# u16c_ubus_rev_b.net
KiCad netlist of a schematic drawn in EAGLE
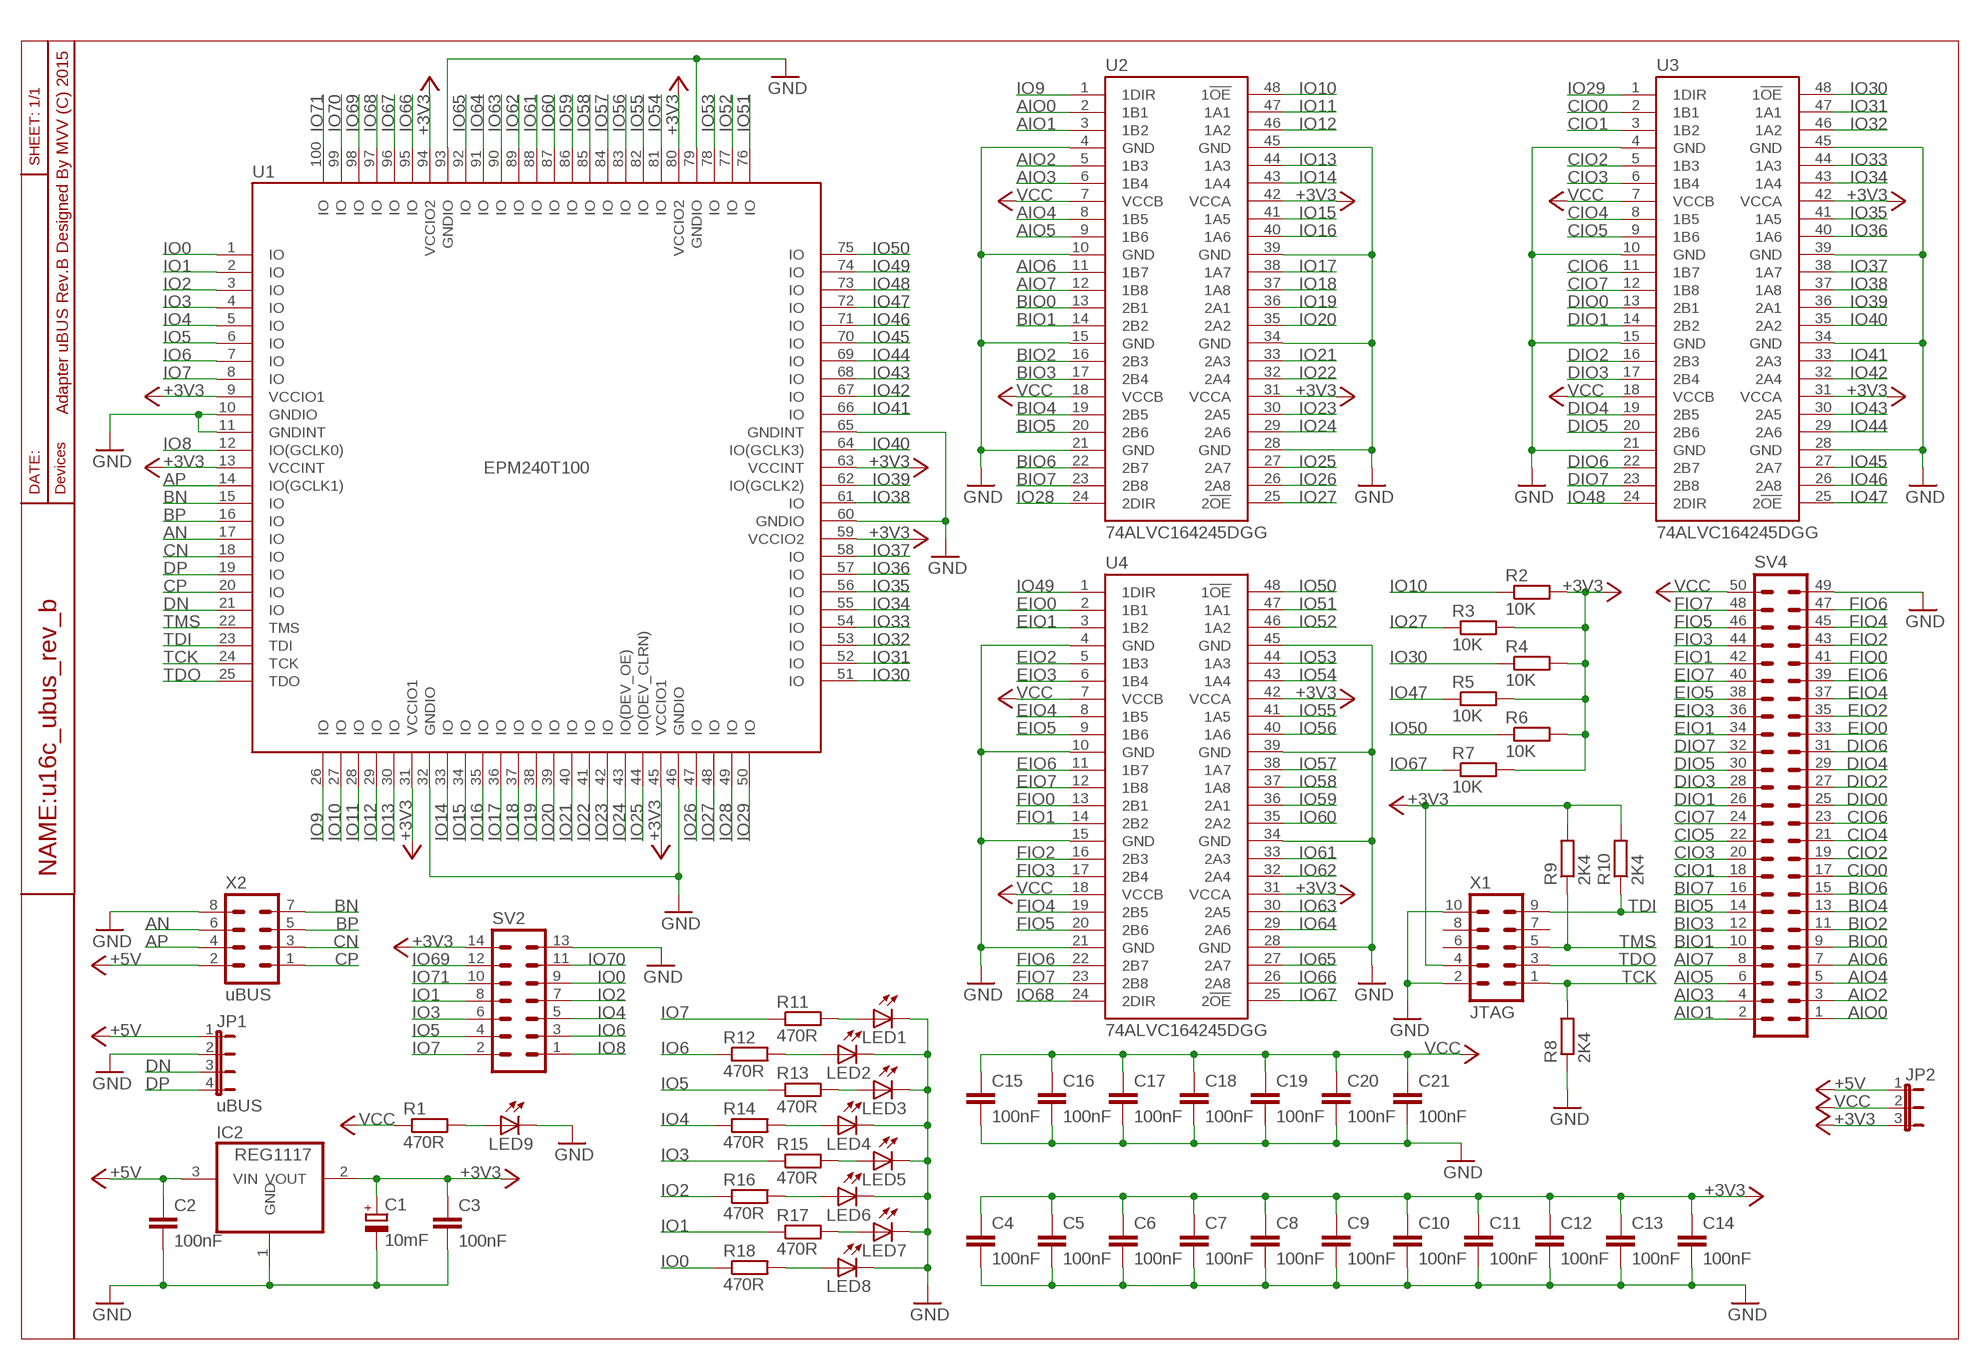
[diagram p0: schematic, sheet 1]

(export (version "E")
  (design (tool "Eeschema 10.0.6"))
  (components
    (comp (ref "C1")
      (value "10mF")
      (footprint "eagle-import:CT6032")
      (libsource (lib "eagle-import") (part "CPOL-EUCT6032"))
    )
    (comp (ref "C2")
      (value "100nF")
      (footprint "eagle-import:C0805")
      (libsource (lib "eagle-import") (part "C-EUC0805"))
    )
    (comp (ref "C3")
      (value "100nF")
      (footprint "eagle-import:C0805")
      (libsource (lib "eagle-import") (part "C-EUC0805"))
    )
    (comp (ref "C4")
      (value "100nF")
      (footprint "eagle-import:C0805")
      (libsource (lib "eagle-import") (part "C-EUC0805"))
    )
    (comp (ref "C5")
      (value "100nF")
      (footprint "eagle-import:C0805")
      (libsource (lib "eagle-import") (part "C-EUC0805"))
    )
    (comp (ref "C6")
      (value "100nF")
      (footprint "eagle-import:C0805")
      (libsource (lib "eagle-import") (part "C-EUC0805"))
    )
    (comp (ref "C7")
      (value "100nF")
      (footprint "eagle-import:C0805")
      (libsource (lib "eagle-import") (part "C-EUC0805"))
    )
    (comp (ref "C8")
      (value "100nF")
      (footprint "eagle-import:C0805")
      (libsource (lib "eagle-import") (part "C-EUC0805"))
    )
    (comp (ref "C9")
      (value "100nF")
      (footprint "eagle-import:C0805")
      (libsource (lib "eagle-import") (part "C-EUC0805"))
    )
    (comp (ref "C10")
      (value "100nF")
      (footprint "eagle-import:C0805")
      (libsource (lib "eagle-import") (part "C-EUC0805"))
    )
    (comp (ref "C11")
      (value "100nF")
      (footprint "eagle-import:C0805")
      (libsource (lib "eagle-import") (part "C-EUC0805"))
    )
    (comp (ref "C12")
      (value "100nF")
      (footprint "eagle-import:C0805")
      (libsource (lib "eagle-import") (part "C-EUC0805"))
    )
    (comp (ref "C13")
      (value "100nF")
      (footprint "eagle-import:C0805")
      (libsource (lib "eagle-import") (part "C-EUC0805"))
    )
    (comp (ref "C14")
      (value "100nF")
      (footprint "eagle-import:C0805")
      (libsource (lib "eagle-import") (part "C-EUC0805"))
    )
    (comp (ref "C15")
      (value "100nF")
      (footprint "eagle-import:C0805")
      (libsource (lib "eagle-import") (part "C-EUC0805"))
    )
    (comp (ref "C16")
      (value "100nF")
      (footprint "eagle-import:C0805")
      (libsource (lib "eagle-import") (part "C-EUC0805"))
    )
    (comp (ref "C17")
      (value "100nF")
      (footprint "eagle-import:C0805")
      (libsource (lib "eagle-import") (part "C-EUC0805"))
    )
    (comp (ref "C18")
      (value "100nF")
      (footprint "eagle-import:C0805")
      (libsource (lib "eagle-import") (part "C-EUC0805"))
    )
    (comp (ref "C19")
      (value "100nF")
      (footprint "eagle-import:C0805")
      (libsource (lib "eagle-import") (part "C-EUC0805"))
    )
    (comp (ref "C20")
      (value "100nF")
      (footprint "eagle-import:C0805")
      (libsource (lib "eagle-import") (part "C-EUC0805"))
    )
    (comp (ref "C21")
      (value "100nF")
      (footprint "eagle-import:C0805")
      (libsource (lib "eagle-import") (part "C-EUC0805"))
    )
    (comp (ref "IC2")
      (value "REG1117")
      (footprint "eagle-import:SOT223")
      (libsource (lib "eagle-import") (part "REG1117"))
    )
    (comp (ref "JP1")
      (value "uBUS")
      (footprint "eagle-import:JP4")
      (libsource (lib "eagle-import") (part "JP4E"))
    )
    (comp (ref "JP2")
      (value "JP2E")
      (footprint "eagle-import:JP2")
      (libsource (lib "eagle-import") (part "JP2E"))
    )
    (comp (ref "LED1")
      (value "LEDCHIPLED_0805")
      (footprint "eagle-import:CHIPLED_0805")
      (libsource (lib "eagle-import") (part "LEDCHIPLED_0805"))
    )
    (comp (ref "LED2")
      (value "LEDCHIPLED_0805")
      (footprint "eagle-import:CHIPLED_0805")
      (libsource (lib "eagle-import") (part "LEDCHIPLED_0805"))
    )
    (comp (ref "LED3")
      (value "LEDCHIPLED_0805")
      (footprint "eagle-import:CHIPLED_0805")
      (libsource (lib "eagle-import") (part "LEDCHIPLED_0805"))
    )
    (comp (ref "LED4")
      (value "LEDCHIPLED_0805")
      (footprint "eagle-import:CHIPLED_0805")
      (libsource (lib "eagle-import") (part "LEDCHIPLED_0805"))
    )
    (comp (ref "LED5")
      (value "LEDCHIPLED_0805")
      (footprint "eagle-import:CHIPLED_0805")
      (libsource (lib "eagle-import") (part "LEDCHIPLED_0805"))
    )
    (comp (ref "LED6")
      (value "LEDCHIPLED_0805")
      (footprint "eagle-import:CHIPLED_0805")
      (libsource (lib "eagle-import") (part "LEDCHIPLED_0805"))
    )
    (comp (ref "LED7")
      (value "LEDCHIPLED_0805")
      (footprint "eagle-import:CHIPLED_0805")
      (libsource (lib "eagle-import") (part "LEDCHIPLED_0805"))
    )
    (comp (ref "LED8")
      (value "LEDCHIPLED_0805")
      (footprint "eagle-import:CHIPLED_0805")
      (libsource (lib "eagle-import") (part "LEDCHIPLED_0805"))
    )
    (comp (ref "LED9")
      (value "LEDCHIPLED_0805")
      (footprint "eagle-import:CHIPLED_0805")
      (libsource (lib "eagle-import") (part "LEDCHIPLED_0805"))
    )
    (comp (ref "R1")
      (value "470R")
      (footprint "eagle-import:R0805")
      (libsource (lib "eagle-import") (part "R-EU_R0805"))
    )
    (comp (ref "R2")
      (value "10K")
      (footprint "eagle-import:R0805")
      (libsource (lib "eagle-import") (part "R-EU_R0805"))
    )
    (comp (ref "R3")
      (value "10K")
      (footprint "eagle-import:R0805")
      (libsource (lib "eagle-import") (part "R-EU_R0805"))
    )
    (comp (ref "R4")
      (value "10K")
      (footprint "eagle-import:R0805")
      (libsource (lib "eagle-import") (part "R-EU_R0805"))
    )
    (comp (ref "R5")
      (value "10K")
      (footprint "eagle-import:R0805")
      (libsource (lib "eagle-import") (part "R-EU_R0805"))
    )
    (comp (ref "R6")
      (value "10K")
      (footprint "eagle-import:R0805")
      (libsource (lib "eagle-import") (part "R-EU_R0805"))
    )
    (comp (ref "R7")
      (value "10K")
      (footprint "eagle-import:R0805")
      (libsource (lib "eagle-import") (part "R-EU_R0805"))
    )
    (comp (ref "R8")
      (value "2K4")
      (footprint "eagle-import:R0805")
      (libsource (lib "eagle-import") (part "R-EU_R0805"))
    )
    (comp (ref "R9")
      (value "2K4")
      (footprint "eagle-import:R0805")
      (libsource (lib "eagle-import") (part "R-EU_R0805"))
    )
    (comp (ref "R10")
      (value "2K4")
      (footprint "eagle-import:R0805")
      (libsource (lib "eagle-import") (part "R-EU_R0805"))
    )
    (comp (ref "R11")
      (value "470R")
      (footprint "eagle-import:R0805")
      (libsource (lib "eagle-import") (part "R-EU_R0805"))
    )
    (comp (ref "R12")
      (value "470R")
      (footprint "eagle-import:R0805")
      (libsource (lib "eagle-import") (part "R-EU_R0805"))
    )
    (comp (ref "R13")
      (value "470R")
      (footprint "eagle-import:R0805")
      (libsource (lib "eagle-import") (part "R-EU_R0805"))
    )
    (comp (ref "R14")
      (value "470R")
      (footprint "eagle-import:R0805")
      (libsource (lib "eagle-import") (part "R-EU_R0805"))
    )
    (comp (ref "R15")
      (value "470R")
      (footprint "eagle-import:R0805")
      (libsource (lib "eagle-import") (part "R-EU_R0805"))
    )
    (comp (ref "R16")
      (value "470R")
      (footprint "eagle-import:R0805")
      (libsource (lib "eagle-import") (part "R-EU_R0805"))
    )
    (comp (ref "R17")
      (value "470R")
      (footprint "eagle-import:R0805")
      (libsource (lib "eagle-import") (part "R-EU_R0805"))
    )
    (comp (ref "R18")
      (value "470R")
      (footprint "eagle-import:R0805")
      (libsource (lib "eagle-import") (part "R-EU_R0805"))
    )
    (comp (ref "SV2")
      (value "ML14")
      (footprint "eagle-import:ML14")
      (libsource (lib "eagle-import") (part "ML14"))
    )
    (comp (ref "SV4")
      (value "ML50")
      (footprint "eagle-import:ML50")
      (libsource (lib "eagle-import") (part "ML50"))
    )
    (comp (ref "U1")
      (value "EPM240T100")
      (footprint "eagle-import:TQFP100")
      (libsource (lib "eagle-import") (part "EPM240T100"))
    )
    (comp (ref "U2")
      (value "74ALVC164245DGG")
      (footprint "eagle-import:TSSOP48DGG")
      (libsource (lib "eagle-import") (part "74ALVC164245DGG"))
    )
    (comp (ref "U3")
      (value "74ALVC164245DGG")
      (footprint "eagle-import:TSSOP48DGG")
      (libsource (lib "eagle-import") (part "74ALVC164245DGG"))
    )
    (comp (ref "U4")
      (value "74ALVC164245DGG")
      (footprint "eagle-import:TSSOP48DGG")
      (libsource (lib "eagle-import") (part "74ALVC164245DGG"))
    )
    (comp (ref "X1")
      (value "JTAG")
      (footprint "eagle-import:ML10")
      (libsource (lib "eagle-import") (part "ML10"))
    )
    (comp (ref "X2")
      (value "uBUS")
      (footprint "eagle-import:MA04-2")
      (libsource (lib "eagle-import") (part "MA04-2"))
    )
  )
  (nets
    (net (code "1") (name "+3V3") (class "Default")
      (node (ref "C1") (pin "+") (pinfunction "+_+") (pintype "passive"))
      (node (ref "C10") (pin "1") (pinfunction "1_1") (pintype "passive"))
      (node (ref "C11") (pin "1") (pinfunction "1_1") (pintype "passive"))
      (node (ref "C12") (pin "1") (pinfunction "1_1") (pintype "passive"))
      (node (ref "C13") (pin "1") (pinfunction "1_1") (pintype "passive"))
      (node (ref "C14") (pin "1") (pinfunction "1_1") (pintype "passive"))
      (node (ref "C3") (pin "1") (pinfunction "1_1") (pintype "passive"))
      (node (ref "C4") (pin "1") (pinfunction "1_1") (pintype "passive"))
      (node (ref "C5") (pin "1") (pinfunction "1_1") (pintype "passive"))
      (node (ref "C6") (pin "1") (pinfunction "1_1") (pintype "passive"))
      (node (ref "C7") (pin "1") (pinfunction "1_1") (pintype "passive"))
      (node (ref "C8") (pin "1") (pinfunction "1_1") (pintype "passive"))
      (node (ref "C9") (pin "1") (pinfunction "1_1") (pintype "passive"))
      (node (ref "IC2") (pin "2") (pinfunction "VOUT_2") (pintype "output"))
      (node (ref "JP2") (pin "3") (pinfunction "3_3") (pintype "passive"))
      (node (ref "R10") (pin "2") (pinfunction "2_2") (pintype "passive"))
      (node (ref "R2") (pin "2") (pinfunction "2_2") (pintype "passive"))
      (node (ref "R3") (pin "2") (pinfunction "2_2") (pintype "passive"))
      (node (ref "R4") (pin "2") (pinfunction "2_2") (pintype "passive"))
      (node (ref "R5") (pin "2") (pinfunction "2_2") (pintype "passive"))
      (node (ref "R6") (pin "2") (pinfunction "2_2") (pintype "passive"))
      (node (ref "R7") (pin "2") (pinfunction "2_2") (pintype "passive"))
      (node (ref "R9") (pin "2") (pinfunction "2_2") (pintype "passive"))
      (node (ref "SV2") (pin "14") (pinfunction "14_14") (pintype "passive"))
      (node (ref "U1") (pin "13") (pinfunction "VCCINT_13") (pintype "power_in"))
      (node (ref "U1") (pin "31") (pinfunction "VCCIO1_31") (pintype "power_in"))
      (node (ref "U1") (pin "45") (pinfunction "VCCIO1_45") (pintype "power_in"))
      (node (ref "U1") (pin "59") (pinfunction "VCCIO2_59") (pintype "power_in"))
      (node (ref "U1") (pin "63") (pinfunction "VCCINT_63") (pintype "power_in"))
      (node (ref "U1") (pin "80") (pinfunction "VCCIO2_80") (pintype "power_in"))
      (node (ref "U1") (pin "9") (pinfunction "VCCIO1_9") (pintype "power_in"))
      (node (ref "U1") (pin "94") (pinfunction "VCCIO2_94") (pintype "power_in"))
      (node (ref "U2") (pin "31") (pinfunction "VCCA_31") (pintype "power_in"))
      (node (ref "U2") (pin "42") (pinfunction "VCCA_42") (pintype "power_in"))
      (node (ref "U3") (pin "31") (pinfunction "VCCA_31") (pintype "power_in"))
      (node (ref "U3") (pin "42") (pinfunction "VCCA_42") (pintype "power_in"))
      (node (ref "U4") (pin "31") (pinfunction "VCCA_31") (pintype "power_in"))
      (node (ref "U4") (pin "42") (pinfunction "VCCA_42") (pintype "power_in"))
      (node (ref "X1") (pin "4") (pinfunction "4_4") (pintype "passive"))
    )
    (net (code "2") (name "+5V") (class "Default")
      (node (ref "C2") (pin "1") (pinfunction "1_1") (pintype "passive"))
      (node (ref "IC2") (pin "3") (pinfunction "VIN_3") (pintype "input"))
      (node (ref "JP1") (pin "1") (pinfunction "1_1") (pintype "passive"))
      (node (ref "JP2") (pin "1") (pinfunction "1_1") (pintype "passive"))
      (node (ref "X2") (pin "2") (pinfunction "2_2") (pintype "passive"))
    )
    (net (code "3") (name "/AIO0") (class "Default")
      (node (ref "SV4") (pin "1") (pinfunction "1_1") (pintype "passive"))
      (node (ref "U2") (pin "2") (pinfunction "1B1_2") (pintype "bidirectional"))
    )
    (net (code "4") (name "/AIO1") (class "Default")
      (node (ref "SV4") (pin "2") (pinfunction "2_2") (pintype "passive"))
      (node (ref "U2") (pin "3") (pinfunction "1B2_3") (pintype "bidirectional"))
    )
    (net (code "5") (name "/AIO2") (class "Default")
      (node (ref "SV4") (pin "3") (pinfunction "3_3") (pintype "passive"))
      (node (ref "U2") (pin "5") (pinfunction "1B3_5") (pintype "bidirectional"))
    )
    (net (code "6") (name "/AIO3") (class "Default")
      (node (ref "SV4") (pin "4") (pinfunction "4_4") (pintype "passive"))
      (node (ref "U2") (pin "6") (pinfunction "1B4_6") (pintype "bidirectional"))
    )
    (net (code "7") (name "/AIO4") (class "Default")
      (node (ref "SV4") (pin "5") (pinfunction "5_5") (pintype "passive"))
      (node (ref "U2") (pin "8") (pinfunction "1B5_8") (pintype "bidirectional"))
    )
    (net (code "8") (name "/AIO5") (class "Default")
      (node (ref "SV4") (pin "6") (pinfunction "6_6") (pintype "passive"))
      (node (ref "U2") (pin "9") (pinfunction "1B6_9") (pintype "bidirectional"))
    )
    (net (code "9") (name "/AIO6") (class "Default")
      (node (ref "SV4") (pin "7") (pinfunction "7_7") (pintype "passive"))
      (node (ref "U2") (pin "11") (pinfunction "1B7_11") (pintype "bidirectional"))
    )
    (net (code "10") (name "/AIO7") (class "Default")
      (node (ref "SV4") (pin "8") (pinfunction "8_8") (pintype "passive"))
      (node (ref "U2") (pin "12") (pinfunction "1B8_12") (pintype "bidirectional"))
    )
    (net (code "11") (name "/AN") (class "Default")
      (node (ref "U1") (pin "17") (pinfunction "IO_17") (pintype "bidirectional"))
      (node (ref "X2") (pin "6") (pinfunction "6_6") (pintype "passive"))
    )
    (net (code "12") (name "/AP") (class "Default")
      (node (ref "U1") (pin "14") (pinfunction "IO(GCLK1)_14") (pintype "bidirectional"))
      (node (ref "X2") (pin "4") (pinfunction "4_4") (pintype "passive"))
    )
    (net (code "13") (name "/BIO0") (class "Default")
      (node (ref "SV4") (pin "9") (pinfunction "9_9") (pintype "passive"))
      (node (ref "U2") (pin "13") (pinfunction "2B1_13") (pintype "bidirectional"))
    )
    (net (code "14") (name "/BIO1") (class "Default")
      (node (ref "SV4") (pin "10") (pinfunction "10_10") (pintype "passive"))
      (node (ref "U2") (pin "14") (pinfunction "2B2_14") (pintype "bidirectional"))
    )
    (net (code "15") (name "/BIO2") (class "Default")
      (node (ref "SV4") (pin "11") (pinfunction "11_11") (pintype "passive"))
      (node (ref "U2") (pin "16") (pinfunction "2B3_16") (pintype "bidirectional"))
    )
    (net (code "16") (name "/BIO3") (class "Default")
      (node (ref "SV4") (pin "12") (pinfunction "12_12") (pintype "passive"))
      (node (ref "U2") (pin "17") (pinfunction "2B4_17") (pintype "bidirectional"))
    )
    (net (code "17") (name "/BIO4") (class "Default")
      (node (ref "SV4") (pin "13") (pinfunction "13_13") (pintype "passive"))
      (node (ref "U2") (pin "19") (pinfunction "2B5_19") (pintype "bidirectional"))
    )
    (net (code "18") (name "/BIO5") (class "Default")
      (node (ref "SV4") (pin "14") (pinfunction "14_14") (pintype "passive"))
      (node (ref "U2") (pin "20") (pinfunction "2B6_20") (pintype "bidirectional"))
    )
    (net (code "19") (name "/BIO6") (class "Default")
      (node (ref "SV4") (pin "15") (pinfunction "15_15") (pintype "passive"))
      (node (ref "U2") (pin "22") (pinfunction "2B7_22") (pintype "bidirectional"))
    )
    (net (code "20") (name "/BIO7") (class "Default")
      (node (ref "SV4") (pin "16") (pinfunction "16_16") (pintype "passive"))
      (node (ref "U2") (pin "23") (pinfunction "2B8_23") (pintype "bidirectional"))
    )
    (net (code "21") (name "/BN") (class "Default")
      (node (ref "U1") (pin "15") (pinfunction "IO_15") (pintype "bidirectional"))
      (node (ref "X2") (pin "7") (pinfunction "7_7") (pintype "passive"))
    )
    (net (code "22") (name "/BP") (class "Default")
      (node (ref "U1") (pin "16") (pinfunction "IO_16") (pintype "bidirectional"))
      (node (ref "X2") (pin "5") (pinfunction "5_5") (pintype "passive"))
    )
    (net (code "23") (name "/CIO0") (class "Default")
      (node (ref "SV4") (pin "17") (pinfunction "17_17") (pintype "passive"))
      (node (ref "U3") (pin "2") (pinfunction "1B1_2") (pintype "bidirectional"))
    )
    (net (code "24") (name "/CIO1") (class "Default")
      (node (ref "SV4") (pin "18") (pinfunction "18_18") (pintype "passive"))
      (node (ref "U3") (pin "3") (pinfunction "1B2_3") (pintype "bidirectional"))
    )
    (net (code "25") (name "/CIO2") (class "Default")
      (node (ref "SV4") (pin "19") (pinfunction "19_19") (pintype "passive"))
      (node (ref "U3") (pin "5") (pinfunction "1B3_5") (pintype "bidirectional"))
    )
    (net (code "26") (name "/CIO3") (class "Default")
      (node (ref "SV4") (pin "20") (pinfunction "20_20") (pintype "passive"))
      (node (ref "U3") (pin "6") (pinfunction "1B4_6") (pintype "bidirectional"))
    )
    (net (code "27") (name "/CIO4") (class "Default")
      (node (ref "SV4") (pin "21") (pinfunction "21_21") (pintype "passive"))
      (node (ref "U3") (pin "8") (pinfunction "1B5_8") (pintype "bidirectional"))
    )
    (net (code "28") (name "/CIO5") (class "Default")
      (node (ref "SV4") (pin "22") (pinfunction "22_22") (pintype "passive"))
      (node (ref "U3") (pin "9") (pinfunction "1B6_9") (pintype "bidirectional"))
    )
    (net (code "29") (name "/CIO6") (class "Default")
      (node (ref "SV4") (pin "23") (pinfunction "23_23") (pintype "passive"))
      (node (ref "U3") (pin "11") (pinfunction "1B7_11") (pintype "bidirectional"))
    )
    (net (code "30") (name "/CIO7") (class "Default")
      (node (ref "SV4") (pin "24") (pinfunction "24_24") (pintype "passive"))
      (node (ref "U3") (pin "12") (pinfunction "1B8_12") (pintype "bidirectional"))
    )
    (net (code "31") (name "/CN") (class "Default")
      (node (ref "U1") (pin "18") (pinfunction "IO_18") (pintype "bidirectional"))
      (node (ref "X2") (pin "3") (pinfunction "3_3") (pintype "passive"))
    )
    (net (code "32") (name "/CP") (class "Default")
      (node (ref "U1") (pin "20") (pinfunction "IO_20") (pintype "bidirectional"))
      (node (ref "X2") (pin "1") (pinfunction "1_1") (pintype "passive"))
    )
    (net (code "33") (name "/DIO0") (class "Default")
      (node (ref "SV4") (pin "25") (pinfunction "25_25") (pintype "passive"))
      (node (ref "U3") (pin "13") (pinfunction "2B1_13") (pintype "bidirectional"))
    )
    (net (code "34") (name "/DIO1") (class "Default")
      (node (ref "SV4") (pin "26") (pinfunction "26_26") (pintype "passive"))
      (node (ref "U3") (pin "14") (pinfunction "2B2_14") (pintype "bidirectional"))
    )
    (net (code "35") (name "/DIO2") (class "Default")
      (node (ref "SV4") (pin "27") (pinfunction "27_27") (pintype "passive"))
      (node (ref "U3") (pin "16") (pinfunction "2B3_16") (pintype "bidirectional"))
    )
    (net (code "36") (name "/DIO3") (class "Default")
      (node (ref "SV4") (pin "28") (pinfunction "28_28") (pintype "passive"))
      (node (ref "U3") (pin "17") (pinfunction "2B4_17") (pintype "bidirectional"))
    )
    (net (code "37") (name "/DIO4") (class "Default")
      (node (ref "SV4") (pin "29") (pinfunction "29_29") (pintype "passive"))
      (node (ref "U3") (pin "19") (pinfunction "2B5_19") (pintype "bidirectional"))
    )
    (net (code "38") (name "/DIO5") (class "Default")
      (node (ref "SV4") (pin "30") (pinfunction "30_30") (pintype "passive"))
      (node (ref "U3") (pin "20") (pinfunction "2B6_20") (pintype "bidirectional"))
    )
    (net (code "39") (name "/DIO6") (class "Default")
      (node (ref "SV4") (pin "31") (pinfunction "31_31") (pintype "passive"))
      (node (ref "U3") (pin "22") (pinfunction "2B7_22") (pintype "bidirectional"))
    )
    (net (code "40") (name "/DIO7") (class "Default")
      (node (ref "SV4") (pin "32") (pinfunction "32_32") (pintype "passive"))
      (node (ref "U3") (pin "23") (pinfunction "2B8_23") (pintype "bidirectional"))
    )
    (net (code "41") (name "/DN") (class "Default")
      (node (ref "JP1") (pin "3") (pinfunction "3_3") (pintype "passive"))
      (node (ref "U1") (pin "21") (pinfunction "IO_21") (pintype "bidirectional"))
    )
    (net (code "42") (name "/DP") (class "Default")
      (node (ref "JP1") (pin "4") (pinfunction "4_4") (pintype "passive"))
      (node (ref "U1") (pin "19") (pinfunction "IO_19") (pintype "bidirectional"))
    )
    (net (code "43") (name "/EIO0") (class "Default")
      (node (ref "SV4") (pin "33") (pinfunction "33_33") (pintype "passive"))
      (node (ref "U4") (pin "2") (pinfunction "1B1_2") (pintype "bidirectional"))
    )
    (net (code "44") (name "/EIO1") (class "Default")
      (node (ref "SV4") (pin "34") (pinfunction "34_34") (pintype "passive"))
      (node (ref "U4") (pin "3") (pinfunction "1B2_3") (pintype "bidirectional"))
    )
    (net (code "45") (name "/EIO2") (class "Default")
      (node (ref "SV4") (pin "35") (pinfunction "35_35") (pintype "passive"))
      (node (ref "U4") (pin "5") (pinfunction "1B3_5") (pintype "bidirectional"))
    )
    (net (code "46") (name "/EIO3") (class "Default")
      (node (ref "SV4") (pin "36") (pinfunction "36_36") (pintype "passive"))
      (node (ref "U4") (pin "6") (pinfunction "1B4_6") (pintype "bidirectional"))
    )
    (net (code "47") (name "/EIO4") (class "Default")
      (node (ref "SV4") (pin "37") (pinfunction "37_37") (pintype "passive"))
      (node (ref "U4") (pin "8") (pinfunction "1B5_8") (pintype "bidirectional"))
    )
    (net (code "48") (name "/EIO5") (class "Default")
      (node (ref "SV4") (pin "38") (pinfunction "38_38") (pintype "passive"))
      (node (ref "U4") (pin "9") (pinfunction "1B6_9") (pintype "bidirectional"))
    )
    (net (code "49") (name "/EIO6") (class "Default")
      (node (ref "SV4") (pin "39") (pinfunction "39_39") (pintype "passive"))
      (node (ref "U4") (pin "11") (pinfunction "1B7_11") (pintype "bidirectional"))
    )
    (net (code "50") (name "/EIO7") (class "Default")
      (node (ref "SV4") (pin "40") (pinfunction "40_40") (pintype "passive"))
      (node (ref "U4") (pin "12") (pinfunction "1B8_12") (pintype "bidirectional"))
    )
    (net (code "51") (name "/FIO0") (class "Default")
      (node (ref "SV4") (pin "41") (pinfunction "41_41") (pintype "passive"))
      (node (ref "U4") (pin "13") (pinfunction "2B1_13") (pintype "bidirectional"))
    )
    (net (code "52") (name "/FIO1") (class "Default")
      (node (ref "SV4") (pin "42") (pinfunction "42_42") (pintype "passive"))
      (node (ref "U4") (pin "14") (pinfunction "2B2_14") (pintype "bidirectional"))
    )
    (net (code "53") (name "/FIO2") (class "Default")
      (node (ref "SV4") (pin "43") (pinfunction "43_43") (pintype "passive"))
      (node (ref "U4") (pin "16") (pinfunction "2B3_16") (pintype "bidirectional"))
    )
    (net (code "54") (name "/FIO3") (class "Default")
      (node (ref "SV4") (pin "44") (pinfunction "44_44") (pintype "passive"))
      (node (ref "U4") (pin "17") (pinfunction "2B4_17") (pintype "bidirectional"))
    )
    (net (code "55") (name "/FIO4") (class "Default")
      (node (ref "SV4") (pin "45") (pinfunction "45_45") (pintype "passive"))
      (node (ref "U4") (pin "19") (pinfunction "2B5_19") (pintype "bidirectional"))
    )
    (net (code "56") (name "/FIO5") (class "Default")
      (node (ref "SV4") (pin "46") (pinfunction "46_46") (pintype "passive"))
      (node (ref "U4") (pin "20") (pinfunction "2B6_20") (pintype "bidirectional"))
    )
    (net (code "57") (name "/FIO6") (class "Default")
      (node (ref "SV4") (pin "47") (pinfunction "47_47") (pintype "passive"))
      (node (ref "U4") (pin "22") (pinfunction "2B7_22") (pintype "bidirectional"))
    )
    (net (code "58") (name "/FIO7") (class "Default")
      (node (ref "SV4") (pin "48") (pinfunction "48_48") (pintype "passive"))
      (node (ref "U4") (pin "23") (pinfunction "2B8_23") (pintype "bidirectional"))
    )
    (net (code "59") (name "/IO0") (class "Default")
      (node (ref "R18") (pin "1") (pinfunction "1_1") (pintype "passive"))
      (node (ref "SV2") (pin "9") (pinfunction "9_9") (pintype "passive"))
      (node (ref "U1") (pin "1") (pinfunction "IO_1") (pintype "bidirectional"))
    )
    (net (code "60") (name "/IO1") (class "Default")
      (node (ref "R17") (pin "1") (pinfunction "1_1") (pintype "passive"))
      (node (ref "SV2") (pin "8") (pinfunction "8_8") (pintype "passive"))
      (node (ref "U1") (pin "2") (pinfunction "IO_2") (pintype "bidirectional"))
    )
    (net (code "61") (name "/IO2") (class "Default")
      (node (ref "R16") (pin "1") (pinfunction "1_1") (pintype "passive"))
      (node (ref "SV2") (pin "7") (pinfunction "7_7") (pintype "passive"))
      (node (ref "U1") (pin "3") (pinfunction "IO_3") (pintype "bidirectional"))
    )
    (net (code "62") (name "/IO3") (class "Default")
      (node (ref "R15") (pin "1") (pinfunction "1_1") (pintype "passive"))
      (node (ref "SV2") (pin "6") (pinfunction "6_6") (pintype "passive"))
      (node (ref "U1") (pin "4") (pinfunction "IO_4") (pintype "bidirectional"))
    )
    (net (code "63") (name "/IO4") (class "Default")
      (node (ref "R14") (pin "1") (pinfunction "1_1") (pintype "passive"))
      (node (ref "SV2") (pin "5") (pinfunction "5_5") (pintype "passive"))
      (node (ref "U1") (pin "5") (pinfunction "IO_5") (pintype "bidirectional"))
    )
    (net (code "64") (name "/IO5") (class "Default")
      (node (ref "R13") (pin "1") (pinfunction "1_1") (pintype "passive"))
      (node (ref "SV2") (pin "4") (pinfunction "4_4") (pintype "passive"))
      (node (ref "U1") (pin "6") (pinfunction "IO_6") (pintype "bidirectional"))
    )
    (net (code "65") (name "/IO6") (class "Default")
      (node (ref "R12") (pin "1") (pinfunction "1_1") (pintype "passive"))
      (node (ref "SV2") (pin "3") (pinfunction "3_3") (pintype "passive"))
      (node (ref "U1") (pin "7") (pinfunction "IO_7") (pintype "bidirectional"))
    )
    (net (code "66") (name "/IO7") (class "Default")
      (node (ref "R11") (pin "1") (pinfunction "1_1") (pintype "passive"))
      (node (ref "SV2") (pin "2") (pinfunction "2_2") (pintype "passive"))
      (node (ref "U1") (pin "8") (pinfunction "IO_8") (pintype "bidirectional"))
    )
    (net (code "67") (name "/IO8") (class "Default")
      (node (ref "SV2") (pin "1") (pinfunction "1_1") (pintype "passive"))
      (node (ref "U1") (pin "12") (pinfunction "IO(GCLK0)_12") (pintype "bidirectional"))
    )
    (net (code "68") (name "/IO9") (class "Default")
      (node (ref "U1") (pin "26") (pinfunction "IO_26") (pintype "bidirectional"))
      (node (ref "U2") (pin "1") (pinfunction "1DIR_1") (pintype "input"))
    )
    (net (code "69") (name "/IO10") (class "Default")
      (node (ref "R2") (pin "1") (pinfunction "1_1") (pintype "passive"))
      (node (ref "U1") (pin "27") (pinfunction "IO_27") (pintype "bidirectional"))
      (node (ref "U2") (pin "48") (pinfunction "1~{OE}_48") (pintype "input"))
    )
    (net (code "70") (name "/IO11") (class "Default")
      (node (ref "U1") (pin "28") (pinfunction "IO_28") (pintype "bidirectional"))
      (node (ref "U2") (pin "47") (pinfunction "1A1_47") (pintype "bidirectional"))
    )
    (net (code "71") (name "/IO12") (class "Default")
      (node (ref "U1") (pin "29") (pinfunction "IO_29") (pintype "bidirectional"))
      (node (ref "U2") (pin "46") (pinfunction "1A2_46") (pintype "bidirectional"))
    )
    (net (code "72") (name "/IO13") (class "Default")
      (node (ref "U1") (pin "30") (pinfunction "IO_30") (pintype "bidirectional"))
      (node (ref "U2") (pin "44") (pinfunction "1A3_44") (pintype "bidirectional"))
    )
    (net (code "73") (name "/IO14") (class "Default")
      (node (ref "U1") (pin "33") (pinfunction "IO_33") (pintype "bidirectional"))
      (node (ref "U2") (pin "43") (pinfunction "1A4_43") (pintype "bidirectional"))
    )
    (net (code "74") (name "/IO15") (class "Default")
      (node (ref "U1") (pin "34") (pinfunction "IO_34") (pintype "bidirectional"))
      (node (ref "U2") (pin "41") (pinfunction "1A5_41") (pintype "bidirectional"))
    )
    (net (code "75") (name "/IO16") (class "Default")
      (node (ref "U1") (pin "35") (pinfunction "IO_35") (pintype "bidirectional"))
      (node (ref "U2") (pin "40") (pinfunction "1A6_40") (pintype "bidirectional"))
    )
    (net (code "76") (name "/IO17") (class "Default")
      (node (ref "U1") (pin "36") (pinfunction "IO_36") (pintype "bidirectional"))
      (node (ref "U2") (pin "38") (pinfunction "1A7_38") (pintype "bidirectional"))
    )
    (net (code "77") (name "/IO18") (class "Default")
      (node (ref "U1") (pin "37") (pinfunction "IO_37") (pintype "bidirectional"))
      (node (ref "U2") (pin "37") (pinfunction "1A8_37") (pintype "bidirectional"))
    )
    (net (code "78") (name "/IO19") (class "Default")
      (node (ref "U1") (pin "38") (pinfunction "IO_38") (pintype "bidirectional"))
      (node (ref "U2") (pin "36") (pinfunction "2A1_36") (pintype "bidirectional"))
    )
    (net (code "79") (name "/IO20") (class "Default")
      (node (ref "U1") (pin "39") (pinfunction "IO_39") (pintype "bidirectional"))
      (node (ref "U2") (pin "35") (pinfunction "2A2_35") (pintype "bidirectional"))
    )
    (net (code "80") (name "/IO21") (class "Default")
      (node (ref "U1") (pin "40") (pinfunction "IO_40") (pintype "bidirectional"))
      (node (ref "U2") (pin "33") (pinfunction "2A3_33") (pintype "bidirectional"))
    )
    (net (code "81") (name "/IO22") (class "Default")
      (node (ref "U1") (pin "41") (pinfunction "IO_41") (pintype "bidirectional"))
      (node (ref "U2") (pin "32") (pinfunction "2A4_32") (pintype "bidirectional"))
    )
    (net (code "82") (name "/IO23") (class "Default")
      (node (ref "U1") (pin "42") (pinfunction "IO_42") (pintype "bidirectional"))
      (node (ref "U2") (pin "30") (pinfunction "2A5_30") (pintype "bidirectional"))
    )
    (net (code "83") (name "/IO24") (class "Default")
      (node (ref "U1") (pin "43") (pinfunction "IO(DEV_OE)_43") (pintype "bidirectional"))
      (node (ref "U2") (pin "29") (pinfunction "2A6_29") (pintype "bidirectional"))
    )
    (net (code "84") (name "/IO25") (class "Default")
      (node (ref "U1") (pin "44") (pinfunction "IO(DEV_CLRN)_44") (pintype "bidirectional"))
      (node (ref "U2") (pin "27") (pinfunction "2A7_27") (pintype "bidirectional"))
    )
    (net (code "85") (name "/IO26") (class "Default")
      (node (ref "U1") (pin "47") (pinfunction "IO_47") (pintype "bidirectional"))
      (node (ref "U2") (pin "26") (pinfunction "2A8_26") (pintype "bidirectional"))
    )
    (net (code "86") (name "/IO27") (class "Default")
      (node (ref "R3") (pin "1") (pinfunction "1_1") (pintype "passive"))
      (node (ref "U1") (pin "48") (pinfunction "IO_48") (pintype "bidirectional"))
      (node (ref "U2") (pin "25") (pinfunction "2~{OE}_25") (pintype "input"))
    )
    (net (code "87") (name "/IO28") (class "Default")
      (node (ref "U1") (pin "49") (pinfunction "IO_49") (pintype "bidirectional"))
      (node (ref "U2") (pin "24") (pinfunction "2DIR_24") (pintype "bidirectional"))
    )
    (net (code "88") (name "/IO29") (class "Default")
      (node (ref "U1") (pin "50") (pinfunction "IO_50") (pintype "bidirectional"))
      (node (ref "U3") (pin "1") (pinfunction "1DIR_1") (pintype "input"))
    )
    (net (code "89") (name "/IO30") (class "Default")
      (node (ref "R4") (pin "1") (pinfunction "1_1") (pintype "passive"))
      (node (ref "U1") (pin "51") (pinfunction "IO_51") (pintype "bidirectional"))
      (node (ref "U3") (pin "48") (pinfunction "1~{OE}_48") (pintype "input"))
    )
    (net (code "90") (name "/IO31") (class "Default")
      (node (ref "U1") (pin "52") (pinfunction "IO_52") (pintype "bidirectional"))
      (node (ref "U3") (pin "47") (pinfunction "1A1_47") (pintype "bidirectional"))
    )
    (net (code "91") (name "/IO32") (class "Default")
      (node (ref "U1") (pin "53") (pinfunction "IO_53") (pintype "bidirectional"))
      (node (ref "U3") (pin "46") (pinfunction "1A2_46") (pintype "bidirectional"))
    )
    (net (code "92") (name "/IO33") (class "Default")
      (node (ref "U1") (pin "54") (pinfunction "IO_54") (pintype "bidirectional"))
      (node (ref "U3") (pin "44") (pinfunction "1A3_44") (pintype "bidirectional"))
    )
    (net (code "93") (name "/IO34") (class "Default")
      (node (ref "U1") (pin "55") (pinfunction "IO_55") (pintype "bidirectional"))
      (node (ref "U3") (pin "43") (pinfunction "1A4_43") (pintype "bidirectional"))
    )
    (net (code "94") (name "/IO35") (class "Default")
      (node (ref "U1") (pin "56") (pinfunction "IO_56") (pintype "bidirectional"))
      (node (ref "U3") (pin "41") (pinfunction "1A5_41") (pintype "bidirectional"))
    )
    (net (code "95") (name "/IO36") (class "Default")
      (node (ref "U1") (pin "57") (pinfunction "IO_57") (pintype "bidirectional"))
      (node (ref "U3") (pin "40") (pinfunction "1A6_40") (pintype "bidirectional"))
    )
    (net (code "96") (name "/IO37") (class "Default")
      (node (ref "U1") (pin "58") (pinfunction "IO_58") (pintype "bidirectional"))
      (node (ref "U3") (pin "38") (pinfunction "1A7_38") (pintype "bidirectional"))
    )
    (net (code "97") (name "/IO38") (class "Default")
      (node (ref "U1") (pin "61") (pinfunction "IO_61") (pintype "bidirectional"))
      (node (ref "U3") (pin "37") (pinfunction "1A8_37") (pintype "bidirectional"))
    )
    (net (code "98") (name "/IO39") (class "Default")
      (node (ref "U1") (pin "62") (pinfunction "IO(GCLK2)_62") (pintype "bidirectional"))
      (node (ref "U3") (pin "36") (pinfunction "2A1_36") (pintype "bidirectional"))
    )
    (net (code "99") (name "/IO40") (class "Default")
      (node (ref "U1") (pin "64") (pinfunction "IO(GCLK3)_64") (pintype "bidirectional"))
      (node (ref "U3") (pin "35") (pinfunction "2A2_35") (pintype "bidirectional"))
    )
    (net (code "100") (name "/IO41") (class "Default")
      (node (ref "U1") (pin "66") (pinfunction "IO_66") (pintype "bidirectional"))
      (node (ref "U3") (pin "33") (pinfunction "2A3_33") (pintype "bidirectional"))
    )
    (net (code "101") (name "/IO42") (class "Default")
      (node (ref "U1") (pin "67") (pinfunction "IO_67") (pintype "bidirectional"))
      (node (ref "U3") (pin "32") (pinfunction "2A4_32") (pintype "bidirectional"))
    )
    (net (code "102") (name "/IO43") (class "Default")
      (node (ref "U1") (pin "68") (pinfunction "IO_68") (pintype "bidirectional"))
      (node (ref "U3") (pin "30") (pinfunction "2A5_30") (pintype "bidirectional"))
    )
    (net (code "103") (name "/IO44") (class "Default")
      (node (ref "U1") (pin "69") (pinfunction "IO_69") (pintype "bidirectional"))
      (node (ref "U3") (pin "29") (pinfunction "2A6_29") (pintype "bidirectional"))
    )
    (net (code "104") (name "/IO45") (class "Default")
      (node (ref "U1") (pin "70") (pinfunction "IO_70") (pintype "bidirectional"))
      (node (ref "U3") (pin "27") (pinfunction "2A7_27") (pintype "bidirectional"))
    )
    (net (code "105") (name "/IO46") (class "Default")
      (node (ref "U1") (pin "71") (pinfunction "IO_71") (pintype "bidirectional"))
      (node (ref "U3") (pin "26") (pinfunction "2A8_26") (pintype "bidirectional"))
    )
    (net (code "106") (name "/IO47") (class "Default")
      (node (ref "R5") (pin "1") (pinfunction "1_1") (pintype "passive"))
      (node (ref "U1") (pin "72") (pinfunction "IO_72") (pintype "bidirectional"))
      (node (ref "U3") (pin "25") (pinfunction "2~{OE}_25") (pintype "input"))
    )
    (net (code "107") (name "/IO48") (class "Default")
      (node (ref "U1") (pin "73") (pinfunction "IO_73") (pintype "bidirectional"))
      (node (ref "U3") (pin "24") (pinfunction "2DIR_24") (pintype "bidirectional"))
    )
    (net (code "108") (name "/IO49") (class "Default")
      (node (ref "U1") (pin "74") (pinfunction "IO_74") (pintype "bidirectional"))
      (node (ref "U4") (pin "1") (pinfunction "1DIR_1") (pintype "input"))
    )
    (net (code "109") (name "/IO50") (class "Default")
      (node (ref "R6") (pin "1") (pinfunction "1_1") (pintype "passive"))
      (node (ref "U1") (pin "75") (pinfunction "IO_75") (pintype "bidirectional"))
      (node (ref "U4") (pin "48") (pinfunction "1~{OE}_48") (pintype "input"))
    )
    (net (code "110") (name "/IO51") (class "Default")
      (node (ref "U1") (pin "76") (pinfunction "IO_76") (pintype "bidirectional"))
      (node (ref "U4") (pin "47") (pinfunction "1A1_47") (pintype "bidirectional"))
    )
    (net (code "111") (name "/IO52") (class "Default")
      (node (ref "U1") (pin "77") (pinfunction "IO_77") (pintype "bidirectional"))
      (node (ref "U4") (pin "46") (pinfunction "1A2_46") (pintype "bidirectional"))
    )
    (net (code "112") (name "/IO53") (class "Default")
      (node (ref "U1") (pin "78") (pinfunction "IO_78") (pintype "bidirectional"))
      (node (ref "U4") (pin "44") (pinfunction "1A3_44") (pintype "bidirectional"))
    )
    (net (code "113") (name "/IO54") (class "Default")
      (node (ref "U1") (pin "81") (pinfunction "IO_81") (pintype "bidirectional"))
      (node (ref "U4") (pin "43") (pinfunction "1A4_43") (pintype "bidirectional"))
    )
    (net (code "114") (name "/IO55") (class "Default")
      (node (ref "U1") (pin "82") (pinfunction "IO_82") (pintype "bidirectional"))
      (node (ref "U4") (pin "41") (pinfunction "1A5_41") (pintype "bidirectional"))
    )
    (net (code "115") (name "/IO56") (class "Default")
      (node (ref "U1") (pin "83") (pinfunction "IO_83") (pintype "bidirectional"))
      (node (ref "U4") (pin "40") (pinfunction "1A6_40") (pintype "bidirectional"))
    )
    (net (code "116") (name "/IO57") (class "Default")
      (node (ref "U1") (pin "84") (pinfunction "IO_84") (pintype "bidirectional"))
      (node (ref "U4") (pin "38") (pinfunction "1A7_38") (pintype "bidirectional"))
    )
    (net (code "117") (name "/IO58") (class "Default")
      (node (ref "U1") (pin "85") (pinfunction "IO_85") (pintype "bidirectional"))
      (node (ref "U4") (pin "37") (pinfunction "1A8_37") (pintype "bidirectional"))
    )
    (net (code "118") (name "/IO59") (class "Default")
      (node (ref "U1") (pin "86") (pinfunction "IO_86") (pintype "bidirectional"))
      (node (ref "U4") (pin "36") (pinfunction "2A1_36") (pintype "bidirectional"))
    )
    (net (code "119") (name "/IO60") (class "Default")
      (node (ref "U1") (pin "87") (pinfunction "IO_87") (pintype "bidirectional"))
      (node (ref "U4") (pin "35") (pinfunction "2A2_35") (pintype "bidirectional"))
    )
    (net (code "120") (name "/IO61") (class "Default")
      (node (ref "U1") (pin "88") (pinfunction "IO_88") (pintype "bidirectional"))
      (node (ref "U4") (pin "33") (pinfunction "2A3_33") (pintype "bidirectional"))
    )
    (net (code "121") (name "/IO62") (class "Default")
      (node (ref "U1") (pin "89") (pinfunction "IO_89") (pintype "bidirectional"))
      (node (ref "U4") (pin "32") (pinfunction "2A4_32") (pintype "bidirectional"))
    )
    (net (code "122") (name "/IO63") (class "Default")
      (node (ref "U1") (pin "90") (pinfunction "IO_90") (pintype "bidirectional"))
      (node (ref "U4") (pin "30") (pinfunction "2A5_30") (pintype "bidirectional"))
    )
    (net (code "123") (name "/IO64") (class "Default")
      (node (ref "U1") (pin "91") (pinfunction "IO_91") (pintype "bidirectional"))
      (node (ref "U4") (pin "29") (pinfunction "2A6_29") (pintype "bidirectional"))
    )
    (net (code "124") (name "/IO65") (class "Default")
      (node (ref "U1") (pin "92") (pinfunction "IO_92") (pintype "bidirectional"))
      (node (ref "U4") (pin "27") (pinfunction "2A7_27") (pintype "bidirectional"))
    )
    (net (code "125") (name "/IO66") (class "Default")
      (node (ref "U1") (pin "95") (pinfunction "IO_95") (pintype "bidirectional"))
      (node (ref "U4") (pin "26") (pinfunction "2A8_26") (pintype "bidirectional"))
    )
    (net (code "126") (name "/IO67") (class "Default")
      (node (ref "R7") (pin "1") (pinfunction "1_1") (pintype "passive"))
      (node (ref "U1") (pin "96") (pinfunction "IO_96") (pintype "bidirectional"))
      (node (ref "U4") (pin "25") (pinfunction "2~{OE}_25") (pintype "input"))
    )
    (net (code "127") (name "/IO68") (class "Default")
      (node (ref "U1") (pin "97") (pinfunction "IO_97") (pintype "bidirectional"))
      (node (ref "U4") (pin "24") (pinfunction "2DIR_24") (pintype "bidirectional"))
    )
    (net (code "128") (name "/IO69") (class "Default")
      (node (ref "SV2") (pin "12") (pinfunction "12_12") (pintype "passive"))
      (node (ref "U1") (pin "98") (pinfunction "IO_98") (pintype "bidirectional"))
    )
    (net (code "129") (name "/IO70") (class "Default")
      (node (ref "SV2") (pin "11") (pinfunction "11_11") (pintype "passive"))
      (node (ref "U1") (pin "99") (pinfunction "IO_99") (pintype "bidirectional"))
    )
    (net (code "130") (name "/IO71") (class "Default")
      (node (ref "SV2") (pin "10") (pinfunction "10_10") (pintype "passive"))
      (node (ref "U1") (pin "100") (pinfunction "IO_100") (pintype "bidirectional"))
    )
    (net (code "131") (name "/TCK") (class "Default")
      (node (ref "R8") (pin "2") (pinfunction "2_2") (pintype "passive"))
      (node (ref "U1") (pin "24") (pinfunction "TCK_24") (pintype "bidirectional"))
      (node (ref "X1") (pin "1") (pinfunction "1_1") (pintype "passive"))
    )
    (net (code "132") (name "/TDI") (class "Default")
      (node (ref "R10") (pin "1") (pinfunction "1_1") (pintype "passive"))
      (node (ref "U1") (pin "23") (pinfunction "TDI_23") (pintype "bidirectional"))
      (node (ref "X1") (pin "9") (pinfunction "9_9") (pintype "passive"))
    )
    (net (code "133") (name "/TDO") (class "Default")
      (node (ref "U1") (pin "25") (pinfunction "TDO_25") (pintype "bidirectional"))
      (node (ref "X1") (pin "3") (pinfunction "3_3") (pintype "passive"))
    )
    (net (code "134") (name "/TMS") (class "Default")
      (node (ref "R9") (pin "1") (pinfunction "1_1") (pintype "passive"))
      (node (ref "U1") (pin "22") (pinfunction "TMS_22") (pintype "bidirectional"))
      (node (ref "X1") (pin "5") (pinfunction "5_5") (pintype "passive"))
    )
    (net (code "135") (name "GND") (class "Default")
      (node (ref "C1") (pin "-") (pinfunction "-_-") (pintype "passive"))
      (node (ref "C10") (pin "2") (pinfunction "2_2") (pintype "passive"))
      (node (ref "C11") (pin "2") (pinfunction "2_2") (pintype "passive"))
      (node (ref "C12") (pin "2") (pinfunction "2_2") (pintype "passive"))
      (node (ref "C13") (pin "2") (pinfunction "2_2") (pintype "passive"))
      (node (ref "C14") (pin "2") (pinfunction "2_2") (pintype "passive"))
      (node (ref "C15") (pin "2") (pinfunction "2_2") (pintype "passive"))
      (node (ref "C16") (pin "2") (pinfunction "2_2") (pintype "passive"))
      (node (ref "C17") (pin "2") (pinfunction "2_2") (pintype "passive"))
      (node (ref "C18") (pin "2") (pinfunction "2_2") (pintype "passive"))
      (node (ref "C19") (pin "2") (pinfunction "2_2") (pintype "passive"))
      (node (ref "C2") (pin "2") (pinfunction "2_2") (pintype "passive"))
      (node (ref "C20") (pin "2") (pinfunction "2_2") (pintype "passive"))
      (node (ref "C21") (pin "2") (pinfunction "2_2") (pintype "passive"))
      (node (ref "C3") (pin "2") (pinfunction "2_2") (pintype "passive"))
      (node (ref "C4") (pin "2") (pinfunction "2_2") (pintype "passive"))
      (node (ref "C5") (pin "2") (pinfunction "2_2") (pintype "passive"))
      (node (ref "C6") (pin "2") (pinfunction "2_2") (pintype "passive"))
      (node (ref "C7") (pin "2") (pinfunction "2_2") (pintype "passive"))
      (node (ref "C8") (pin "2") (pinfunction "2_2") (pintype "passive"))
      (node (ref "C9") (pin "2") (pinfunction "2_2") (pintype "passive"))
      (node (ref "IC2") (pin "1") (pinfunction "GND_1") (pintype "power_in"))
      (node (ref "JP1") (pin "2") (pinfunction "2_2") (pintype "passive"))
      (node (ref "LED1") (pin "C") (pinfunction "C_C") (pintype "passive"))
      (node (ref "LED2") (pin "C") (pinfunction "C_C") (pintype "passive"))
      (node (ref "LED3") (pin "C") (pinfunction "C_C") (pintype "passive"))
      (node (ref "LED4") (pin "C") (pinfunction "C_C") (pintype "passive"))
      (node (ref "LED5") (pin "C") (pinfunction "C_C") (pintype "passive"))
      (node (ref "LED6") (pin "C") (pinfunction "C_C") (pintype "passive"))
      (node (ref "LED7") (pin "C") (pinfunction "C_C") (pintype "passive"))
      (node (ref "LED8") (pin "C") (pinfunction "C_C") (pintype "passive"))
      (node (ref "LED9") (pin "C") (pinfunction "C_C") (pintype "passive"))
      (node (ref "R8") (pin "1") (pinfunction "1_1") (pintype "passive"))
      (node (ref "SV2") (pin "13") (pinfunction "13_13") (pintype "passive"))
      (node (ref "SV4") (pin "49") (pinfunction "49_49") (pintype "passive"))
      (node (ref "U1") (pin "10") (pinfunction "GNDIO_10") (pintype "power_in"))
      (node (ref "U1") (pin "11") (pinfunction "GNDINT_11") (pintype "power_in"))
      (node (ref "U1") (pin "32") (pinfunction "GNDIO_32") (pintype "power_in"))
      (node (ref "U1") (pin "46") (pinfunction "GNDIO_46") (pintype "power_in"))
      (node (ref "U1") (pin "60") (pinfunction "GNDIO_60") (pintype "power_in"))
      (node (ref "U1") (pin "65") (pinfunction "GNDINT_65") (pintype "power_in"))
      (node (ref "U1") (pin "79") (pinfunction "GNDIO_79") (pintype "power_in"))
      (node (ref "U1") (pin "93") (pinfunction "GNDIO_93") (pintype "power_in"))
      (node (ref "U2") (pin "10") (pinfunction "GND_10") (pintype "bidirectional"))
      (node (ref "U2") (pin "15") (pinfunction "GND_15") (pintype "bidirectional"))
      (node (ref "U2") (pin "21") (pinfunction "GND_21") (pintype "power_in"))
      (node (ref "U2") (pin "28") (pinfunction "GND_28") (pintype "power_in"))
      (node (ref "U2") (pin "34") (pinfunction "GND_34") (pintype "power_in"))
      (node (ref "U2") (pin "39") (pinfunction "GND_39") (pintype "power_in"))
      (node (ref "U2") (pin "4") (pinfunction "GND_4") (pintype "power_in"))
      (node (ref "U2") (pin "45") (pinfunction "GND_45") (pintype "power_in"))
      (node (ref "U3") (pin "10") (pinfunction "GND_10") (pintype "bidirectional"))
      (node (ref "U3") (pin "15") (pinfunction "GND_15") (pintype "bidirectional"))
      (node (ref "U3") (pin "21") (pinfunction "GND_21") (pintype "power_in"))
      (node (ref "U3") (pin "28") (pinfunction "GND_28") (pintype "power_in"))
      (node (ref "U3") (pin "34") (pinfunction "GND_34") (pintype "power_in"))
      (node (ref "U3") (pin "39") (pinfunction "GND_39") (pintype "power_in"))
      (node (ref "U3") (pin "4") (pinfunction "GND_4") (pintype "power_in"))
      (node (ref "U3") (pin "45") (pinfunction "GND_45") (pintype "power_in"))
      (node (ref "U4") (pin "10") (pinfunction "GND_10") (pintype "bidirectional"))
      (node (ref "U4") (pin "15") (pinfunction "GND_15") (pintype "bidirectional"))
      (node (ref "U4") (pin "21") (pinfunction "GND_21") (pintype "power_in"))
      (node (ref "U4") (pin "28") (pinfunction "GND_28") (pintype "power_in"))
      (node (ref "U4") (pin "34") (pinfunction "GND_34") (pintype "power_in"))
      (node (ref "U4") (pin "39") (pinfunction "GND_39") (pintype "power_in"))
      (node (ref "U4") (pin "4") (pinfunction "GND_4") (pintype "power_in"))
      (node (ref "U4") (pin "45") (pinfunction "GND_45") (pintype "power_in"))
      (node (ref "X1") (pin "10") (pinfunction "10_10") (pintype "passive"))
      (node (ref "X1") (pin "2") (pinfunction "2_2") (pintype "passive"))
      (node (ref "X2") (pin "8") (pinfunction "8_8") (pintype "passive"))
    )
    (net (code "136") (name "Net-(LED1-PadA)") (class "Default")
      (node (ref "LED1") (pin "A") (pinfunction "A_A") (pintype "passive"))
      (node (ref "R11") (pin "2") (pinfunction "2_2") (pintype "passive"))
    )
    (net (code "137") (name "Net-(LED2-PadA)") (class "Default")
      (node (ref "LED2") (pin "A") (pinfunction "A_A") (pintype "passive"))
      (node (ref "R12") (pin "2") (pinfunction "2_2") (pintype "passive"))
    )
    (net (code "138") (name "Net-(LED3-PadA)") (class "Default")
      (node (ref "LED3") (pin "A") (pinfunction "A_A") (pintype "passive"))
      (node (ref "R13") (pin "2") (pinfunction "2_2") (pintype "passive"))
    )
    (net (code "139") (name "Net-(LED4-PadA)") (class "Default")
      (node (ref "LED4") (pin "A") (pinfunction "A_A") (pintype "passive"))
      (node (ref "R14") (pin "2") (pinfunction "2_2") (pintype "passive"))
    )
    (net (code "140") (name "Net-(LED5-PadA)") (class "Default")
      (node (ref "LED5") (pin "A") (pinfunction "A_A") (pintype "passive"))
      (node (ref "R15") (pin "2") (pinfunction "2_2") (pintype "passive"))
    )
    (net (code "141") (name "Net-(LED6-PadA)") (class "Default")
      (node (ref "LED6") (pin "A") (pinfunction "A_A") (pintype "passive"))
      (node (ref "R16") (pin "2") (pinfunction "2_2") (pintype "passive"))
    )
    (net (code "142") (name "Net-(LED7-PadA)") (class "Default")
      (node (ref "LED7") (pin "A") (pinfunction "A_A") (pintype "passive"))
      (node (ref "R17") (pin "2") (pinfunction "2_2") (pintype "passive"))
    )
    (net (code "143") (name "Net-(LED8-PadA)") (class "Default")
      (node (ref "LED8") (pin "A") (pinfunction "A_A") (pintype "passive"))
      (node (ref "R18") (pin "2") (pinfunction "2_2") (pintype "passive"))
    )
    (net (code "144") (name "Net-(LED9-PadA)") (class "Default")
      (node (ref "LED9") (pin "A") (pinfunction "A_A") (pintype "passive"))
      (node (ref "R1") (pin "2") (pinfunction "2_2") (pintype "passive"))
    )
    (net (code "145") (name "VCC") (class "Default")
      (node (ref "C15") (pin "1") (pinfunction "1_1") (pintype "passive"))
      (node (ref "C16") (pin "1") (pinfunction "1_1") (pintype "passive"))
      (node (ref "C17") (pin "1") (pinfunction "1_1") (pintype "passive"))
      (node (ref "C18") (pin "1") (pinfunction "1_1") (pintype "passive"))
      (node (ref "C19") (pin "1") (pinfunction "1_1") (pintype "passive"))
      (node (ref "C20") (pin "1") (pinfunction "1_1") (pintype "passive"))
      (node (ref "C21") (pin "1") (pinfunction "1_1") (pintype "passive"))
      (node (ref "JP2") (pin "2") (pinfunction "2_2") (pintype "passive"))
      (node (ref "R1") (pin "1") (pinfunction "1_1") (pintype "passive"))
      (node (ref "SV4") (pin "50") (pinfunction "50_50") (pintype "passive"))
      (node (ref "U2") (pin "18") (pinfunction "VCCB_18") (pintype "power_in"))
      (node (ref "U2") (pin "7") (pinfunction "VCCB_7") (pintype "power_in"))
      (node (ref "U3") (pin "18") (pinfunction "VCCB_18") (pintype "power_in"))
      (node (ref "U3") (pin "7") (pinfunction "VCCB_7") (pintype "power_in"))
      (node (ref "U4") (pin "18") (pinfunction "VCCB_18") (pintype "power_in"))
      (node (ref "U4") (pin "7") (pinfunction "VCCB_7") (pintype "power_in"))
    )
    (net (code "146") (name "unconnected-(X1-Pad6)") (class "Default")
      (node (ref "X1") (pin "6") (pinfunction "6_6") (pintype "passive"))
    )
    (net (code "147") (name "unconnected-(X1-Pad7)") (class "Default")
      (node (ref "X1") (pin "7") (pinfunction "7_7") (pintype "passive"))
    )
    (net (code "148") (name "unconnected-(X1-Pad8)") (class "Default")
      (node (ref "X1") (pin "8") (pinfunction "8_8") (pintype "passive"))
    )
  )
)
